# Telemetria.net
KiCad netlist of a schematic drawn in EAGLE
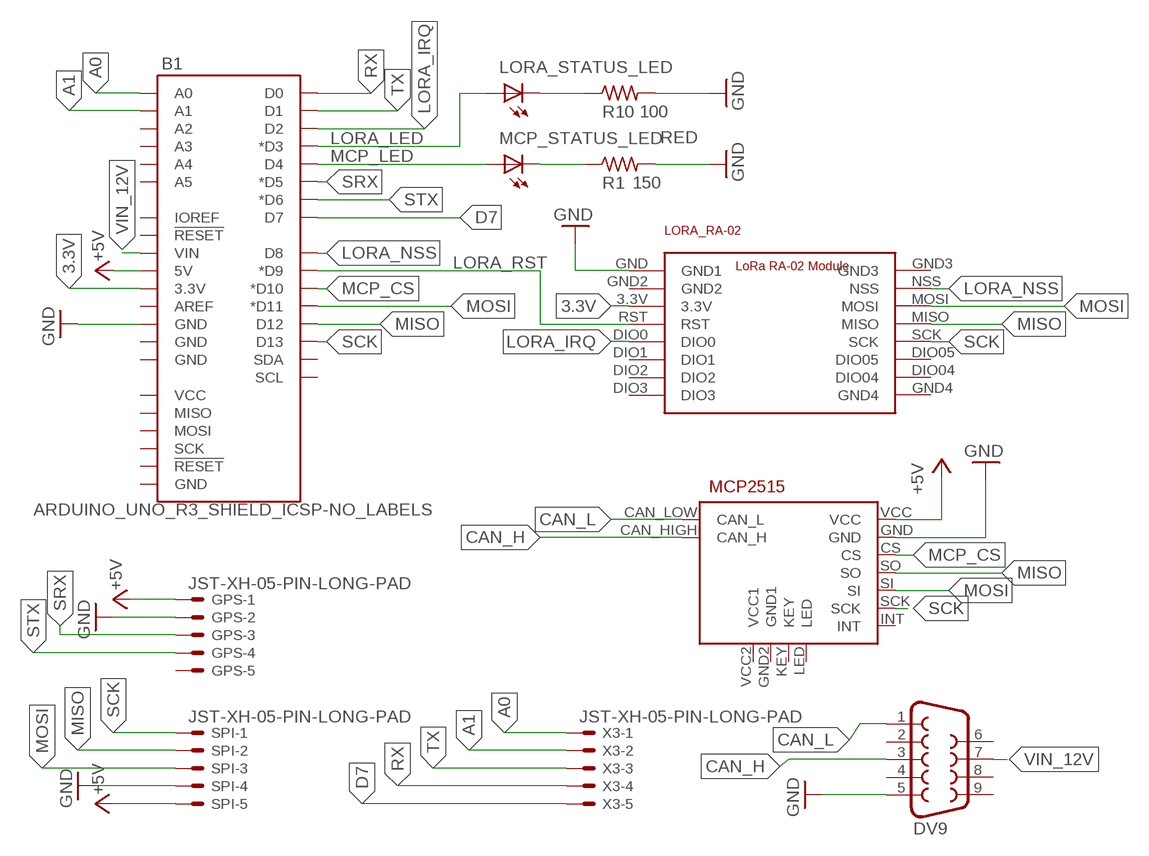
[diagram p0: schematic, sheet 1]

(export (version "E")
  (design (tool "Eeschema 10.0.6"))
  (components
    (comp (ref "B1")
      (value "ARDUINO_UNO_R3_SHIELD_ICSP-NO_LABELS")
      (footprint "eagle-import:UNO_R3_SHIELD_ICSP_NOLABELS")
      (libsource (lib "eagle-import") (part "ARDUINO_UNO_R3_SHIELD_ICSP-NO_LABELS"))
    )
    (comp (ref "GPS")
      (value "JST-XH-05-PIN-LONG-PAD")
      (footprint "eagle-import:JST-XH-05-PACKAGE-LONG-PAD")
      (libsource (lib "eagle-import") (part "JST-XH-05-PIN-LONG-PAD"))
    )
    (comp (ref "LORA_RA-02")
      (value "LORA_RA-02_MODULE")
      (footprint "eagle-import:LORA_RA-02_MODULE_FOOTPRINT")
      (libsource (lib "eagle-import") (part "LORA_RA-02_MODULE"))
    )
    (comp (ref "LORA_STATUS_LED")
      (value "BLUE")
      (footprint "eagle-import:CHIP-LED0805")
      (libsource (lib "eagle-import") (part "LEDCHIP-LED0805"))
    )
    (comp (ref "MCP2515")
      (value "MCP2515")
      (footprint "eagle-import:MCP2515")
      (libsource (lib "eagle-import") (part "MCP2515"))
    )
    (comp (ref "MCP_STATUS_LED")
      (value "RED")
      (footprint "eagle-import:CHIP-LED0805")
      (libsource (lib "eagle-import") (part "LEDCHIP-LED0805"))
    )
    (comp (ref "R1")
      (value "150")
      (footprint "eagle-import:M0805")
      (libsource (lib "eagle-import") (part "R-US_M0805"))
    )
    (comp (ref "R10")
      (value "100")
      (footprint "eagle-import:M0805")
      (libsource (lib "eagle-import") (part "R-US_M0805"))
    )
    (comp (ref "SPI")
      (value "JST-XH-05-PIN-LONG-PAD")
      (footprint "eagle-import:JST-XH-05-PACKAGE-LONG-PAD")
      (libsource (lib "eagle-import") (part "JST-XH-05-PIN-LONG-PAD"))
    )
    (comp (ref "X3")
      (value "JST-XH-05-PIN-LONG-PAD")
      (footprint "eagle-import:JST-XH-05-PACKAGE-LONG-PAD")
      (libsource (lib "eagle-import") (part "JST-XH-05-PIN-LONG-PAD"))
    )
    (comp (ref "X4")
      (value "DV9")
      (footprint "eagle-import:F09H")
      (libsource (lib "eagle-import") (part "F09H"))
    )
  )
  (nets
    (net (code "1") (name "+5V") (class "Default")
      (node (ref "B1") (pin "5V") (pinfunction "5V_5V") (pintype "bidirectional"))
      (node (ref "GPS") (pin "1") (pinfunction "S_1") (pintype "passive"))
      (node (ref "MCP2515") (pin "VCC") (pinfunction "VCC_VCC") (pintype "bidirectional"))
      (node (ref "SPI") (pin "5") (pinfunction "S_5") (pintype "passive"))
    )
    (net (code "2") (name "/LORA_LED") (class "Default")
      (node (ref "B1") (pin "D3") (pinfunction "*D3_D3") (pintype "bidirectional"))
      (node (ref "LORA_STATUS_LED") (pin "A") (pinfunction "A_A") (pintype "passive"))
    )
    (net (code "3") (name "/LORA_RST") (class "Default")
      (node (ref "B1") (pin "D9") (pinfunction "*D9_D9") (pintype "bidirectional"))
      (node (ref "LORA_RA-02") (pin "RST") (pinfunction "RST_RST") (pintype "bidirectional"))
    )
    (net (code "4") (name "/MCP_LED") (class "Default")
      (node (ref "B1") (pin "D4") (pinfunction "D4_D4") (pintype "bidirectional"))
      (node (ref "MCP_STATUS_LED") (pin "A") (pinfunction "A_A") (pintype "passive"))
    )
    (net (code "5") (name "3.3V") (class "Default")
      (node (ref "B1") (pin "3.3V") (pinfunction "3.3V_3.3V") (pintype "bidirectional"))
      (node (ref "LORA_RA-02") (pin "3.3V") (pinfunction "3.3V_3.3V") (pintype "bidirectional"))
    )
    (net (code "6") (name "A0") (class "Default")
      (node (ref "B1") (pin "A0") (pinfunction "A0_A0") (pintype "bidirectional"))
      (node (ref "X3") (pin "1") (pinfunction "S_1") (pintype "passive"))
    )
    (net (code "7") (name "A1") (class "Default")
      (node (ref "B1") (pin "A1") (pinfunction "A1_A1") (pintype "bidirectional"))
      (node (ref "X3") (pin "2") (pinfunction "S_2") (pintype "passive"))
    )
    (net (code "8") (name "CAN_H") (class "Default")
      (node (ref "MCP2515") (pin "CAN_HIGH") (pinfunction "CAN_H_CAN_HIGH") (pintype "bidirectional"))
      (node (ref "X4") (pin "3") (pinfunction "3_3") (pintype "passive"))
    )
    (net (code "9") (name "CAN_L") (class "Default")
      (node (ref "MCP2515") (pin "CAN_LOW") (pinfunction "CAN_L_CAN_LOW") (pintype "bidirectional"))
      (node (ref "X4") (pin "1") (pinfunction "1_1") (pintype "passive"))
    )
    (net (code "10") (name "D7") (class "Default")
      (node (ref "B1") (pin "D7") (pinfunction "D7_D7") (pintype "bidirectional"))
      (node (ref "X3") (pin "5") (pinfunction "S_5") (pintype "passive"))
    )
    (net (code "11") (name "GND") (class "Default")
      (node (ref "B1") (pin "GND@2") (pinfunction "GND_GND@2") (pintype "bidirectional"))
      (node (ref "GPS") (pin "2") (pinfunction "S_2") (pintype "passive"))
      (node (ref "LORA_RA-02") (pin "GND") (pinfunction "GND1_GND") (pintype "bidirectional"))
      (node (ref "MCP2515") (pin "GND") (pinfunction "GND_GND") (pintype "bidirectional"))
      (node (ref "R1") (pin "2") (pinfunction "2_2") (pintype "passive"))
      (node (ref "R10") (pin "2") (pinfunction "2_2") (pintype "passive"))
      (node (ref "SPI") (pin "4") (pinfunction "S_4") (pintype "passive"))
      (node (ref "X4") (pin "5") (pinfunction "5_5") (pintype "passive"))
    )
    (net (code "12") (name "LORA_IRQ") (class "Default")
      (node (ref "B1") (pin "D2") (pinfunction "D2_D2") (pintype "bidirectional"))
      (node (ref "LORA_RA-02") (pin "DIO0") (pinfunction "DIO0_DIO0") (pintype "bidirectional"))
    )
    (net (code "13") (name "LORA_NSS") (class "Default")
      (node (ref "B1") (pin "D8") (pinfunction "D8_D8") (pintype "bidirectional"))
      (node (ref "LORA_RA-02") (pin "NSS") (pinfunction "NSS_NSS") (pintype "bidirectional"))
    )
    (net (code "14") (name "MCP_CS") (class "Default")
      (node (ref "B1") (pin "D10") (pinfunction "*D10_D10") (pintype "bidirectional"))
      (node (ref "MCP2515") (pin "CS") (pinfunction "CS_CS") (pintype "bidirectional"))
    )
    (net (code "15") (name "MISO") (class "Default")
      (node (ref "B1") (pin "D12") (pinfunction "D12_D12") (pintype "bidirectional"))
      (node (ref "LORA_RA-02") (pin "MISO") (pinfunction "MISO_MISO") (pintype "bidirectional"))
      (node (ref "MCP2515") (pin "SO") (pinfunction "SO_SO") (pintype "bidirectional"))
      (node (ref "SPI") (pin "2") (pinfunction "S_2") (pintype "passive"))
    )
    (net (code "16") (name "MOSI") (class "Default")
      (node (ref "B1") (pin "D11") (pinfunction "*D11_D11") (pintype "bidirectional"))
      (node (ref "LORA_RA-02") (pin "MOSI") (pinfunction "MOSI_MOSI") (pintype "bidirectional"))
      (node (ref "MCP2515") (pin "SI") (pinfunction "SI_SI") (pintype "bidirectional"))
      (node (ref "SPI") (pin "3") (pinfunction "S_3") (pintype "passive"))
    )
    (net (code "17") (name "Net-(LORA_STATUS_LED-PadC)") (class "Default")
      (node (ref "LORA_STATUS_LED") (pin "C") (pinfunction "C_C") (pintype "passive"))
      (node (ref "R10") (pin "1") (pinfunction "1_1") (pintype "passive"))
    )
    (net (code "18") (name "Net-(MCP_STATUS_LED-PadC)") (class "Default")
      (node (ref "MCP_STATUS_LED") (pin "C") (pinfunction "C_C") (pintype "passive"))
      (node (ref "R1") (pin "1") (pinfunction "1_1") (pintype "passive"))
    )
    (net (code "19") (name "RX") (class "Default")
      (node (ref "B1") (pin "RX") (pinfunction "D0_RX") (pintype "bidirectional"))
      (node (ref "X3") (pin "4") (pinfunction "S_4") (pintype "passive"))
    )
    (net (code "20") (name "SCK") (class "Default")
      (node (ref "B1") (pin "D13") (pinfunction "D13_D13") (pintype "bidirectional"))
      (node (ref "LORA_RA-02") (pin "SCK") (pinfunction "SCK_SCK") (pintype "bidirectional"))
      (node (ref "MCP2515") (pin "SCK") (pinfunction "SCK_SCK") (pintype "bidirectional"))
      (node (ref "SPI") (pin "1") (pinfunction "S_1") (pintype "passive"))
    )
    (net (code "21") (name "SRX") (class "Default")
      (node (ref "B1") (pin "D5") (pinfunction "*D5_D5") (pintype "bidirectional"))
      (node (ref "GPS") (pin "3") (pinfunction "S_3") (pintype "passive"))
    )
    (net (code "22") (name "STX") (class "Default")
      (node (ref "B1") (pin "D6") (pinfunction "*D6_D6") (pintype "bidirectional"))
      (node (ref "GPS") (pin "4") (pinfunction "S_4") (pintype "passive"))
    )
    (net (code "23") (name "TX") (class "Default")
      (node (ref "B1") (pin "TX") (pinfunction "D1_TX") (pintype "bidirectional"))
      (node (ref "X3") (pin "3") (pinfunction "S_3") (pintype "passive"))
    )
    (net (code "24") (name "VIN_12V") (class "Default")
      (node (ref "B1") (pin "VIN") (pinfunction "VIN_VIN") (pintype "bidirectional"))
      (node (ref "X4") (pin "7") (pinfunction "7_7") (pintype "passive"))
    )
    (net (code "25") (name "unconnected-(B1-GND-PadGND@0)") (class "Default")
      (node (ref "B1") (pin "GND@0") (pinfunction "GND_GND@0") (pintype "bidirectional"))
    )
    (net (code "26") (name "unconnected-(B1-GND-PadGND@1)") (class "Default")
      (node (ref "B1") (pin "GND@1") (pinfunction "GND_GND@1") (pintype "bidirectional"))
    )
    (net (code "27") (name "unconnected-(B1-GND-PadGND_ICSP)") (class "Default")
      (node (ref "B1") (pin "GND_ICSP") (pinfunction "GND_GND_ICSP") (pintype "bidirectional"))
    )
    (net (code "28") (name "unconnected-(B1-PadA2)") (class "Default")
      (node (ref "B1") (pin "A2") (pinfunction "A2_A2") (pintype "bidirectional"))
    )
    (net (code "29") (name "unconnected-(B1-PadA3)") (class "Default")
      (node (ref "B1") (pin "A3") (pinfunction "A3_A3") (pintype "bidirectional"))
    )
    (net (code "30") (name "unconnected-(B1-PadA4)") (class "Default")
      (node (ref "B1") (pin "A4") (pinfunction "A4_A4") (pintype "bidirectional"))
    )
    (net (code "31") (name "unconnected-(B1-PadA5)") (class "Default")
      (node (ref "B1") (pin "A5") (pinfunction "A5_A5") (pintype "bidirectional"))
    )
    (net (code "32") (name "unconnected-(B1-PadAREF)") (class "Default")
      (node (ref "B1") (pin "AREF") (pinfunction "AREF_AREF") (pintype "bidirectional"))
    )
    (net (code "33") (name "unconnected-(B1-PadIOREF)") (class "Default")
      (node (ref "B1") (pin "IOREF") (pinfunction "IOREF_IOREF") (pintype "bidirectional"))
    )
    (net (code "34") (name "unconnected-(B1-PadMISO)") (class "Default")
      (node (ref "B1") (pin "MISO") (pinfunction "MISO_MISO") (pintype "bidirectional"))
    )
    (net (code "35") (name "unconnected-(B1-PadMOSI)") (class "Default")
      (node (ref "B1") (pin "MOSI") (pinfunction "MOSI_MOSI") (pintype "bidirectional"))
    )
    (net (code "36") (name "unconnected-(B1-PadSCK)") (class "Default")
      (node (ref "B1") (pin "SCK") (pinfunction "SCK_SCK") (pintype "bidirectional"))
    )
    (net (code "37") (name "unconnected-(B1-PadSCL)") (class "Default")
      (node (ref "B1") (pin "SCL") (pinfunction "SCL_SCL") (pintype "bidirectional"))
    )
    (net (code "38") (name "unconnected-(B1-PadSDA)") (class "Default")
      (node (ref "B1") (pin "SDA") (pinfunction "SDA_SDA") (pintype "bidirectional"))
    )
    (net (code "39") (name "unconnected-(B1-VCC-Pad5V_ICSP)") (class "Default")
      (node (ref "B1") (pin "5V_ICSP") (pinfunction "VCC_5V_ICSP") (pintype "bidirectional"))
    )
    (net (code "40") (name "unconnected-(B1-~{RESET}-PadRES)") (class "Default")
      (node (ref "B1") (pin "RES") (pinfunction "~{RESET}_RES") (pintype "bidirectional"))
    )
    (net (code "41") (name "unconnected-(B1-~{RESET}-PadRST_ICSP)") (class "Default")
      (node (ref "B1") (pin "RST_ICSP") (pinfunction "~{RESET}_RST_ICSP") (pintype "bidirectional"))
    )
    (net (code "42") (name "unconnected-(GPSE-S-Pad5)") (class "Default")
      (node (ref "GPS") (pin "5") (pinfunction "S_5") (pintype "passive"))
    )
    (net (code "43") (name "unconnected-(LORA_RA-02-PadDIO1)") (class "Default")
      (node (ref "LORA_RA-02") (pin "DIO1") (pinfunction "DIO1_DIO1") (pintype "bidirectional"))
    )
    (net (code "44") (name "unconnected-(LORA_RA-02-PadDIO2)") (class "Default")
      (node (ref "LORA_RA-02") (pin "DIO2") (pinfunction "DIO2_DIO2") (pintype "bidirectional"))
    )
    (net (code "45") (name "unconnected-(LORA_RA-02-PadDIO3)") (class "Default")
      (node (ref "LORA_RA-02") (pin "DIO3") (pinfunction "DIO3_DIO3") (pintype "bidirectional"))
    )
    (net (code "46") (name "unconnected-(LORA_RA-02-PadDIO04)") (class "Default")
      (node (ref "LORA_RA-02") (pin "DIO04") (pinfunction "DIO04_DIO04") (pintype "bidirectional"))
    )
    (net (code "47") (name "unconnected-(LORA_RA-02-PadDIO05)") (class "Default")
      (node (ref "LORA_RA-02") (pin "DIO05") (pinfunction "DIO05_DIO05") (pintype "bidirectional"))
    )
    (net (code "48") (name "unconnected-(LORA_RA-02-PadGND2)") (class "Default")
      (node (ref "LORA_RA-02") (pin "GND2") (pinfunction "GND2_GND2") (pintype "bidirectional"))
    )
    (net (code "49") (name "unconnected-(LORA_RA-02-PadGND3)") (class "Default")
      (node (ref "LORA_RA-02") (pin "GND3") (pinfunction "GND3_GND3") (pintype "bidirectional"))
    )
    (net (code "50") (name "unconnected-(LORA_RA-02-PadGND4)") (class "Default")
      (node (ref "LORA_RA-02") (pin "GND4") (pinfunction "GND4_GND4") (pintype "bidirectional"))
    )
    (net (code "51") (name "unconnected-(MCP2515-GND1-PadGND2)") (class "Default")
      (node (ref "MCP2515") (pin "GND2") (pinfunction "GND1_GND2") (pintype "bidirectional"))
    )
    (net (code "52") (name "unconnected-(MCP2515-PadINT)") (class "Default")
      (node (ref "MCP2515") (pin "INT") (pinfunction "INT_INT") (pintype "bidirectional"))
    )
    (net (code "53") (name "unconnected-(MCP2515-PadKEY)") (class "Default")
      (node (ref "MCP2515") (pin "KEY") (pinfunction "KEY_KEY") (pintype "bidirectional"))
    )
    (net (code "54") (name "unconnected-(MCP2515-PadLED)") (class "Default")
      (node (ref "MCP2515") (pin "LED") (pinfunction "LED_LED") (pintype "bidirectional"))
    )
    (net (code "55") (name "unconnected-(MCP2515-VCC1-PadVCC2)") (class "Default")
      (node (ref "MCP2515") (pin "VCC2") (pinfunction "VCC1_VCC2") (pintype "bidirectional"))
    )
    (net (code "56") (name "unconnected-(X4-Pad2)") (class "Default")
      (node (ref "X4") (pin "2") (pinfunction "2_2") (pintype "passive"))
    )
    (net (code "57") (name "unconnected-(X4-Pad4)") (class "Default")
      (node (ref "X4") (pin "4") (pinfunction "4_4") (pintype "passive"))
    )
    (net (code "58") (name "unconnected-(X4-Pad6)") (class "Default")
      (node (ref "X4") (pin "6") (pinfunction "6_6") (pintype "passive"))
    )
    (net (code "59") (name "unconnected-(X4-Pad8)") (class "Default")
      (node (ref "X4") (pin "8") (pinfunction "8_8") (pintype "passive"))
    )
    (net (code "60") (name "unconnected-(X4-Pad9)") (class "Default")
      (node (ref "X4") (pin "9") (pinfunction "9_9") (pintype "passive"))
    )
  )
)
